# ESP32_USB.net
KiCad netlist of a schematic drawn in Altium Designer
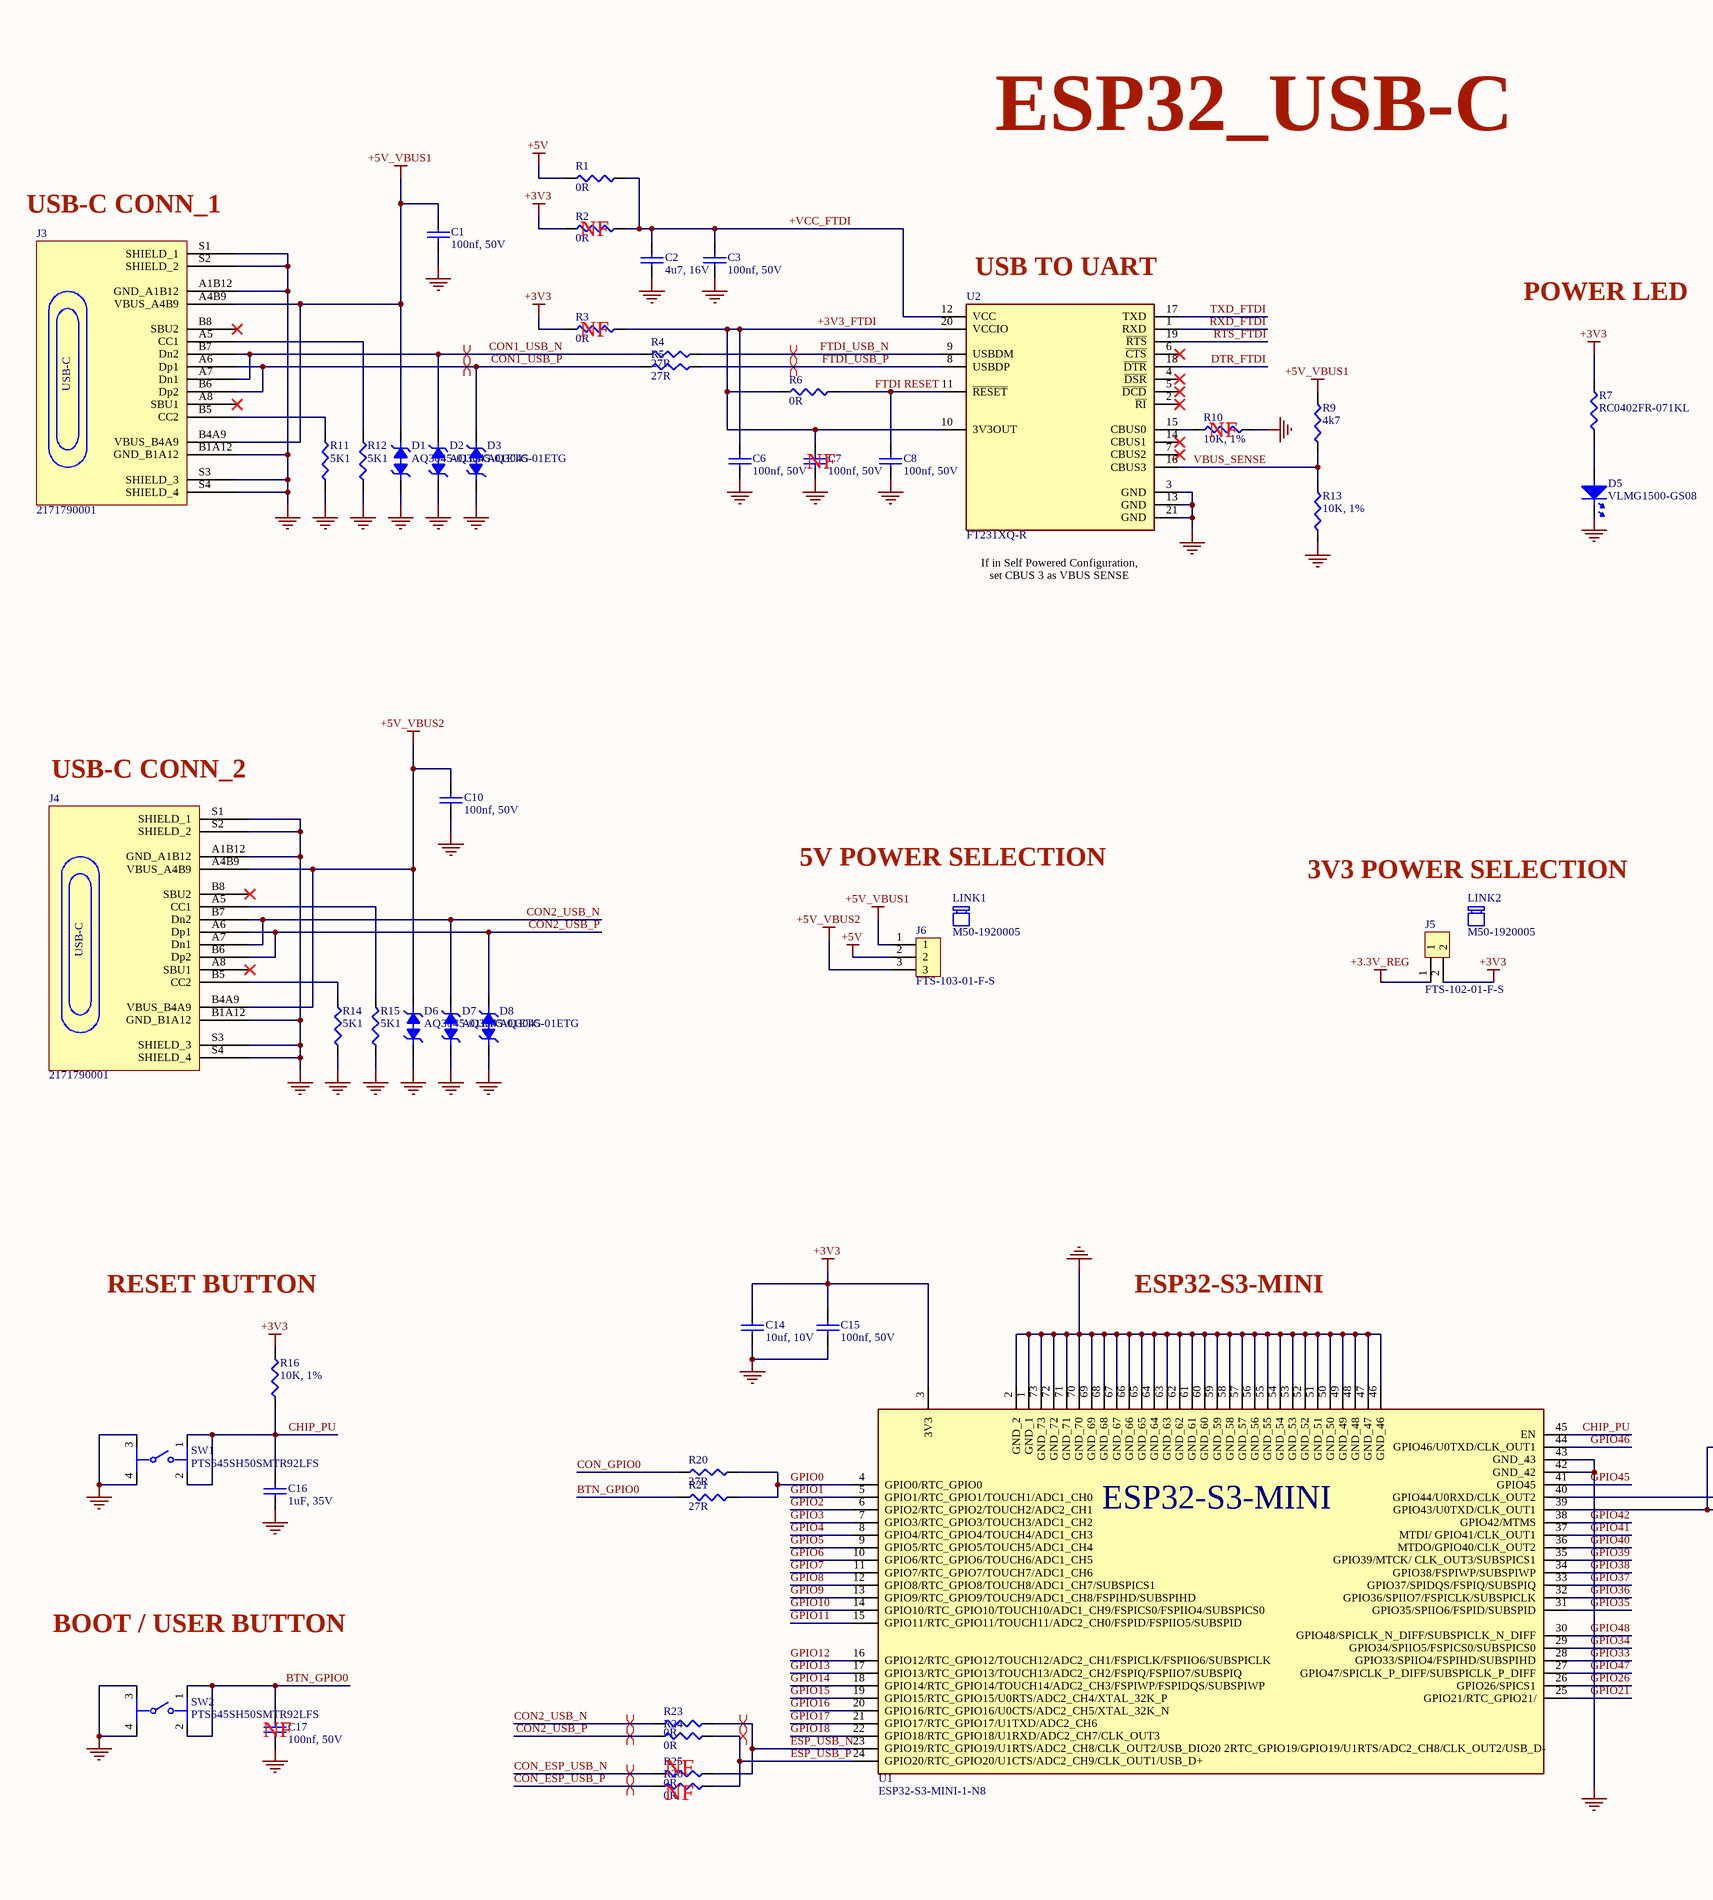
[diagram p0: ESP32_USB.SchDoc, left]
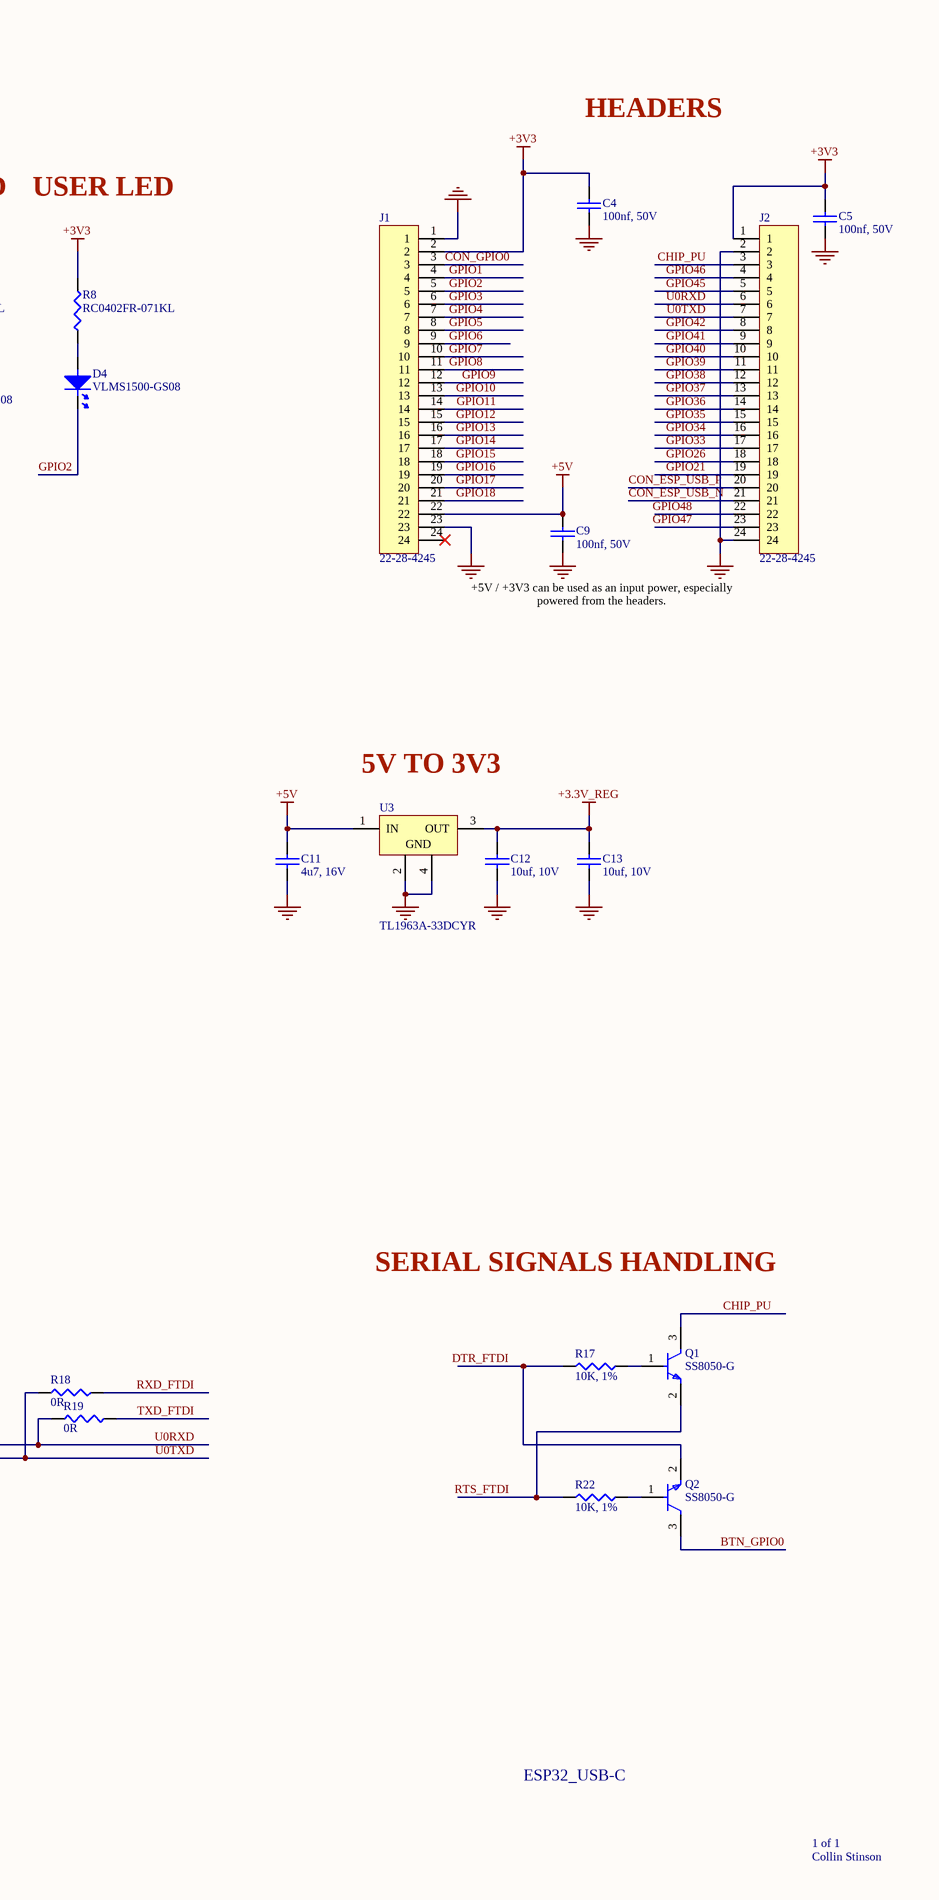
[diagram p1: ESP32_USB.SchDoc, right]

(export (version "E")
  (design (tool "Eeschema 10.0.6"))
  (components
    (comp (ref "C1")
      (value "100nf, 50V")
      (footprint "CAPC1005X65N")
      (fields
        (field (name "MANUFACTURER") "Samsung")
        (field (name "MANUFACTURER PART NUMBER") "CL05B104KB54PNC")
        (field (name "LCSC PART NO") "C307331")
      )
      (libsource (lib "ESP32_USB") (part "CL05B104KB54PNC"))
    )
    (comp (ref "C2")
      (value "4u7, 16V")
      (footprint "CAPC1005X65N")
      (fields
        (field (name "MANUFACTURER") "Samsung")
        (field (name "MANUFACTURER PART NUMBER") "CL05A475MO5NUNC")
        (field (name "LCSC PART NO") "C318563")
      )
      (libsource (lib "ESP32_USB") (part "CL05A475MO5NUNC"))
    )
    (comp (ref "C3")
      (value "100nf, 50V")
      (footprint "CAPC1005X65N")
      (fields
        (field (name "MANUFACTURER") "Samsung")
        (field (name "MANUFACTURER PART NUMBER") "CL05B104KB54PNC")
        (field (name "LCSC PART NO") "C307331")
      )
      (libsource (lib "ESP32_USB") (part "CL05B104KB54PNC"))
    )
    (comp (ref "C4")
      (value "100nf, 50V")
      (footprint "CAPC1005X65N")
      (fields
        (field (name "MANUFACTURER") "Samsung")
        (field (name "MANUFACTURER PART NUMBER") "CL05B104KB54PNC")
        (field (name "LCSC PART NO") "C307331")
      )
      (libsource (lib "ESP32_USB") (part "CL05B104KB54PNC"))
    )
    (comp (ref "C5")
      (value "100nf, 50V")
      (footprint "CAPC1005X65N")
      (fields
        (field (name "MANUFACTURER") "Samsung")
        (field (name "MANUFACTURER PART NUMBER") "CL05B104KB54PNC")
        (field (name "LCSC PART NO") "C307331")
      )
      (libsource (lib "ESP32_USB") (part "CL05B104KB54PNC"))
    )
    (comp (ref "C6")
      (value "100nf, 50V")
      (footprint "CAPC1005X65N")
      (fields
        (field (name "MANUFACTURER") "Samsung")
        (field (name "MANUFACTURER PART NUMBER") "CL05B104KB54PNC")
        (field (name "LCSC PART NO") "C307331")
      )
      (libsource (lib "ESP32_USB") (part "CL05B104KB54PNC"))
    )
    (comp (ref "C7")
      (value "100nf, 50V")
      (footprint "CAPC1005X65N")
      (fields
        (field (name "MANUFACTURER") "Samsung")
        (field (name "MANUFACTURER PART NUMBER") "CL05B104KB54PNC")
        (field (name "LCSC PART NO") "C307331")
      )
      (libsource (lib "ESP32_USB") (part "CL05B104KB54PNC"))
    )
    (comp (ref "C8")
      (value "100nf, 50V")
      (footprint "CAPC1005X65N")
      (fields
        (field (name "MANUFACTURER") "Samsung")
        (field (name "MANUFACTURER PART NUMBER") "CL05B104KB54PNC")
        (field (name "LCSC PART NO") "C307331")
      )
      (libsource (lib "ESP32_USB") (part "CL05B104KB54PNC"))
    )
    (comp (ref "C9")
      (value "100nf, 50V")
      (footprint "CAPC1005X65N")
      (fields
        (field (name "MANUFACTURER") "Samsung")
        (field (name "MANUFACTURER PART NUMBER") "CL05B104KB54PNC")
        (field (name "LCSC PART NO") "C307331")
      )
      (libsource (lib "ESP32_USB") (part "CL05B104KB54PNC"))
    )
    (comp (ref "C10")
      (value "100nf, 50V")
      (footprint "CAPC1005X65N")
      (fields
        (field (name "MANUFACTURER") "Samsung")
        (field (name "MANUFACTURER PART NUMBER") "CL05B104KB54PNC")
        (field (name "LCSC PART NO") "C307331")
      )
      (libsource (lib "ESP32_USB") (part "CL05B104KB54PNC"))
    )
    (comp (ref "C11")
      (value "4u7, 16V")
      (footprint "CAPC1005X65N")
      (fields
        (field (name "MANUFACTURER") "Samsung")
        (field (name "MANUFACTURER PART NUMBER") "CL05A475MO5NUNC")
        (field (name "LCSC PART NO") "C318563")
      )
      (libsource (lib "ESP32_USB") (part "CL05A475MO5NUNC"))
    )
    (comp (ref "C12")
      (value "10uf, 10V")
      (footprint "CAPC1005X65N")
      (fields
        (field (name "MANUFACTURER") "Samsung")
        (field (name "MANUFACTURER PART NUMBER") "CL05A106MP8NUB8")
        (field (name "LCSC PART NO") "C307415")
      )
      (libsource (lib "ESP32_USB") (part "CL05A106MP8NUB8"))
    )
    (comp (ref "C13")
      (value "10uf, 10V")
      (footprint "CAPC1005X65N")
      (fields
        (field (name "MANUFACTURER") "Samsung")
        (field (name "MANUFACTURER PART NUMBER") "CL05A106MP8NUB8")
        (field (name "LCSC PART NO") "C307415")
      )
      (libsource (lib "ESP32_USB") (part "CL05A106MP8NUB8"))
    )
    (comp (ref "C14")
      (value "10uf, 10V")
      (footprint "CAPC1005X65N")
      (fields
        (field (name "MANUFACTURER") "Samsung")
        (field (name "MANUFACTURER PART NUMBER") "CL05A106MP8NUB8")
        (field (name "LCSC PART NO") "C307415")
      )
      (libsource (lib "ESP32_USB") (part "CL05A106MP8NUB8"))
    )
    (comp (ref "C15")
      (value "100nf, 50V")
      (footprint "CAPC1005X65N")
      (fields
        (field (name "MANUFACTURER") "Samsung")
        (field (name "MANUFACTURER PART NUMBER") "CL05B104KB54PNC")
        (field (name "LCSC PART NO") "C307331")
      )
      (libsource (lib "ESP32_USB") (part "CL05B104KB54PNC"))
    )
    (comp (ref "C16")
      (value "1uF, 35V")
      (footprint "CAPC1005X65N")
      (fields
        (field (name "MANUFACTURER") "Samsung")
        (field (name "MANUFACTURER PART NUMBER") "CL05A105KL5NRNC")
        (field (name "LCSC PART NO") "C307413")
      )
      (libsource (lib "ESP32_USB") (part "CL05A105KL5NRNC"))
    )
    (comp (ref "C17")
      (value "100nf, 50V")
      (footprint "CAPC1005X65N")
      (fields
        (field (name "MANUFACTURER") "Samsung")
        (field (name "MANUFACTURER PART NUMBER") "CL05B104KB54PNC")
        (field (name "LCSC PART NO") "C307331")
      )
      (libsource (lib "ESP32_USB") (part "CL05B104KB54PNC"))
    )
    (comp (ref "D1")
      (value "AQ3045-01ETG")
      (footprint "SOD882")
      (description "Trans Voltage Suppressor Diode, 40W, 5.3V V(RWM), Bidirectional, 1 Element, Silicon, MO-236")
      (fields (field (name "MANUFACTURER") "Littelfuse") (field (name "LCSC PART NO") "C3710326"))
      (libsource (lib "ESP32_USB") (part "AQ3045-01ETG"))
    )
    (comp (ref "D2")
      (value "AQ3045-01ETG")
      (footprint "SOD882")
      (description "Trans Voltage Suppressor Diode, 40W, 5.3V V(RWM), Bidirectional, 1 Element, Silicon, MO-236")
      (fields (field (name "MANUFACTURER") "Littelfuse") (field (name "LCSC PART NO") "C3710326"))
      (libsource (lib "ESP32_USB") (part "AQ3045-01ETG"))
    )
    (comp (ref "D3")
      (value "AQ3045-01ETG")
      (footprint "SOD882")
      (description "Trans Voltage Suppressor Diode, 40W, 5.3V V(RWM), Bidirectional, 1 Element, Silicon, MO-236")
      (fields (field (name "MANUFACTURER") "Littelfuse") (field (name "LCSC PART NO") "C3710326"))
      (libsource (lib "ESP32_USB") (part "AQ3045-01ETG"))
    )
    (comp (ref "D4")
      (value "VLMS1500-GS08")
      (footprint "LEDC1005X35N")
      (description "Single Color LED, Super Red, 0.5mm")
      (fields (field (name "MANUFACTURER") "Vishay") (field (name "LCSC PART NO") "C511370"))
      (libsource (lib "ESP32_USB") (part "VLMS1500-GS08"))
    )
    (comp (ref "D5")
      (value "VLMG1500-GS08")
      (footprint "LEDC1005X35N")
      (description "Single Color LED, Yellow Green, 0.5mm")
      (fields (field (name "MANUFACTURER") "Vishay") (field (name "LCSC PART NO") "C511404"))
      (libsource (lib "ESP32_USB") (part "VLMG1500-GS08"))
    )
    (comp (ref "D6")
      (value "AQ3045-01ETG")
      (footprint "SOD882")
      (description "Trans Voltage Suppressor Diode, 40W, 5.3V V(RWM), Bidirectional, 1 Element, Silicon, MO-236")
      (fields (field (name "MANUFACTURER") "Littelfuse") (field (name "LCSC PART NO") "C3710326"))
      (libsource (lib "ESP32_USB") (part "AQ3045-01ETG"))
    )
    (comp (ref "D7")
      (value "AQ3045-01ETG")
      (footprint "SOD882")
      (description "Trans Voltage Suppressor Diode, 40W, 5.3V V(RWM), Bidirectional, 1 Element, Silicon, MO-236")
      (fields (field (name "MANUFACTURER") "Littelfuse") (field (name "LCSC PART NO") "C3710326"))
      (libsource (lib "ESP32_USB") (part "AQ3045-01ETG"))
    )
    (comp (ref "D8")
      (value "AQ3045-01ETG")
      (footprint "SOD882")
      (description "Trans Voltage Suppressor Diode, 40W, 5.3V V(RWM), Bidirectional, 1 Element, Silicon, MO-236")
      (fields (field (name "MANUFACTURER") "Littelfuse") (field (name "LCSC PART NO") "C3710326"))
      (libsource (lib "ESP32_USB") (part "AQ3045-01ETG"))
    )
    (comp (ref "J1")
      (value "22-28-4245")
      (footprint "HDR_1X24_2.54MM")
      (description "Conn Unshrouded Header HDR 24 POS 2.54mm Solder ST Thru-Hole KK® Bag")
      (fields (field (name "MANUFACTURER") "Molex") (field (name "LCSC PART NO") "C7145888"))
      (libsource (lib "ESP32_USB") (part "22-28-4245"))
    )
    (comp (ref "J2")
      (value "22-28-4245")
      (footprint "HDR_1X24_2.54MM")
      (description "Conn Unshrouded Header HDR 24 POS 2.54mm Solder ST Thru-Hole KK® Bag")
      (fields (field (name "MANUFACTURER") "Molex") (field (name "LCSC PART NO") "C7145888"))
      (libsource (lib "") (part "22-28-4245_1"))
    )
    (comp (ref "J3")
      (value "2171790001")
      (footprint "FP-2171790001-MFG")
      (description "USB Connector, 16 Contact(s), Female, Right Angle, Surface Mount Terminal, Locking, Receptacle")
      (fields (field (name "MANUFACTURER") "Molex") (field (name "MANUFACTURER PART NUMBER") "217179-0001"))
      (libsource (lib "ESP32_USB") (part "217179-0001"))
    )
    (comp (ref "J4")
      (value "2171790001")
      (footprint "FP-2171790001-MFG")
      (description "USB Connector, 16 Contact(s), Female, Right Angle, Surface Mount Terminal, Locking, Receptacle")
      (fields (field (name "MANUFACTURER") "Molex") (field (name "MANUFACTURER PART NUMBER") "217179-0001"))
      (libsource (lib "ESP32_USB") (part "217179-0001"))
    )
    (comp (ref "J5")
      (value "FTS-102-01-F-S")
      (footprint "HDR_1X2_1.27MM")
      (description "Board Connector, 2 Contact(s), 1 Row(s), Male, Straight, Solder Terminal")
      (fields (field (name "MANUFACTURER") "Samtec") (field (name "LCSC PART NO") "C6045317"))
      (libsource (lib "ESP32_USB") (part "FTS-102-01-F-S"))
    )
    (comp (ref "J6")
      (value "FTS-103-01-F-S")
      (footprint "HDR_1X3_1.27MM")
      (description "Board Connector, 3 Contact(s), 1 Row(s), Male, Straight, Solder Terminal")
      (fields (field (name "MANUFACTURER") "Samtec") (field (name "LCSC PART NO") "C3333578"))
      (libsource (lib "ESP32_USB") (part "FTS-103-01-F-S"))
    )
    (comp (ref "LINK1")
      (value "M50-1920005")
      (description "Interconnection Device")
      (fields (field (name "MANUFACTURER") "Harwin") (field (name "LCSC PART NO") "C6985646"))
      (libsource (lib "ESP32_USB") (part "M50-1920005"))
    )
    (comp (ref "LINK2")
      (value "M50-1920005")
      (description "Interconnection Device")
      (fields (field (name "MANUFACTURER") "Harwin") (field (name "LCSC PART NO") "C6985646"))
      (libsource (lib "ESP32_USB") (part "M50-1920005"))
    )
    (comp (ref "Q1")
      (value "SS8050-G")
      (footprint "FP-SS8050-G-IPC_B")
      (description "Small Signal Bipolar Transistor, 1.5A I(C), 25V V(BR)CEO, 1-Element, NPN, Silicon")
      (fields (field (name "MANUFACTURER") "Comchip") (field (name "LCSC PART NO") "C164886"))
      (libsource (lib "ESP32_USB") (part "SS8050-G"))
    )
    (comp (ref "Q2")
      (value "SS8050-G")
      (footprint "FP-SS8050-G-IPC_B")
      (description "Small Signal Bipolar Transistor, 1.5A I(C), 25V V(BR)CEO, 1-Element, NPN, Silicon")
      (fields (field (name "MANUFACTURER") "Comchip") (field (name "LCSC PART NO") "C164886"))
      (libsource (lib "ESP32_USB") (part "SS8050-G"))
    )
    (comp (ref "R1")
      (value "0R")
      (footprint "RESC1005X37N")
      (description "Metal Glaze/thick Film, 0.0625W, 0ohm, Surface Mount, 0402")
      (fields
        (field (name "MANUFACTURER") "Yageo")
        (field (name "MANUFACTURER PART NUMBER") "RC0402JR-070RL")
      )
      (libsource (lib "ESP32_USB") (part "RC0402JR-070RL"))
    )
    (comp (ref "R2")
      (value "0R")
      (footprint "RESC1005X37N")
      (description "Metal Glaze/thick Film, 0.0625W, 0ohm, Surface Mount, 0402")
      (fields
        (field (name "MANUFACTURER") "Yageo")
        (field (name "MANUFACTURER PART NUMBER") "RC0402JR-070RL")
      )
      (libsource (lib "ESP32_USB") (part "RC0402JR-070RL"))
    )
    (comp (ref "R3")
      (value "0R")
      (footprint "RESC1005X37N")
      (description "Metal Glaze/thick Film, 0.0625W, 0ohm, Surface Mount, 0402")
      (fields
        (field (name "MANUFACTURER") "Yageo")
        (field (name "MANUFACTURER PART NUMBER") "RC0402JR-070RL")
      )
      (libsource (lib "ESP32_USB") (part "RC0402JR-070RL"))
    )
    (comp (ref "R4")
      (value "27R")
      (footprint "RESC1005X37N")
      (fields
        (field (name "MANUFACTURER") "Yageo")
        (field (name "MANUFACTURER PART NUMBER") "RC0402FR-0727RL")
        (field (name "TOLERANCE") "1%")
      )
      (libsource (lib "ESP32_USB") (part "RC0402FR-0727RL"))
    )
    (comp (ref "R5")
      (value "27R")
      (footprint "RESC1005X37N")
      (fields
        (field (name "MANUFACTURER") "Yageo")
        (field (name "MANUFACTURER PART NUMBER") "RC0402FR-0727RL")
        (field (name "TOLERANCE") "1%")
      )
      (libsource (lib "ESP32_USB") (part "RC0402FR-0727RL"))
    )
    (comp (ref "R6")
      (value "0R")
      (footprint "RESC1005X37N")
      (description "Metal Glaze/thick Film, 0.0625W, 0ohm, Surface Mount, 0402")
      (fields
        (field (name "MANUFACTURER") "Yageo")
        (field (name "MANUFACTURER PART NUMBER") "RC0402JR-070RL")
      )
      (libsource (lib "ESP32_USB") (part "RC0402JR-070RL"))
    )
    (comp (ref "R7")
      (value "RC0402FR-071KL")
      (footprint "RESC1005X37N")
      (fields
        (field (name "MANUFACTURER") "Yageo")
        (field (name "TOLERANCE") "1%")
        (field (name "POWER") "62.5mW")
      )
      (libsource (lib "ESP32_USB") (part "RC0402FR-071KL"))
    )
    (comp (ref "R8")
      (value "RC0402FR-071KL")
      (footprint "RESC1005X37N")
      (fields
        (field (name "MANUFACTURER") "Yageo")
        (field (name "TOLERANCE") "1%")
        (field (name "POWER") "62.5mW")
      )
      (libsource (lib "ESP32_USB") (part "RC0402FR-071KL"))
    )
    (comp (ref "R9")
      (value "4k7")
      (footprint "RESC1005X37N")
      (fields
        (field (name "MANUFACTURER") "Yageo")
        (field (name "MANUFACTURER PART NUMBER") "RC0402FR-074K7L")
        (field (name "TOLERANCE") "1%")
      )
      (libsource (lib "ESP32_USB") (part "RC0402FR-074K7L"))
    )
    (comp (ref "R10")
      (value "10K, 1%")
      (footprint "RESC1005X37N")
      (fields
        (field (name "MANUFACTURER") "Yageo")
        (field (name "MANUFACTURER PART NUMBER") "AC0402FR-0710KL")
        (field (name "TOLERANCE") "1%")
      )
      (libsource (lib "ESP32_USB") (part "AC0402FR-0710KL"))
    )
    (comp (ref "R11")
      (value "5K1")
      (footprint "RESC1005X37N")
      (fields
        (field (name "MANUFACTURER") "Yageo")
        (field (name "MANUFACTURER PART NUMBER") "AC0402FR-075K1L")
        (field (name "TOLERANCE") "1%")
      )
      (libsource (lib "ESP32_USB") (part "AC0402FR-075K1L"))
    )
    (comp (ref "R12")
      (value "5K1")
      (footprint "RESC1005X37N")
      (fields
        (field (name "MANUFACTURER") "Yageo")
        (field (name "MANUFACTURER PART NUMBER") "AC0402FR-075K1L")
        (field (name "TOLERANCE") "1%")
      )
      (libsource (lib "ESP32_USB") (part "AC0402FR-075K1L"))
    )
    (comp (ref "R13")
      (value "10K, 1%")
      (footprint "RESC1005X37N")
      (fields
        (field (name "MANUFACTURER") "Yageo")
        (field (name "MANUFACTURER PART NUMBER") "AC0402FR-0710KL")
        (field (name "TOLERANCE") "1%")
      )
      (libsource (lib "ESP32_USB") (part "AC0402FR-0710KL"))
    )
    (comp (ref "R14")
      (value "5K1")
      (footprint "RESC1005X37N")
      (fields
        (field (name "MANUFACTURER") "Yageo")
        (field (name "MANUFACTURER PART NUMBER") "AC0402FR-075K1L")
        (field (name "TOLERANCE") "1%")
      )
      (libsource (lib "ESP32_USB") (part "AC0402FR-075K1L"))
    )
    (comp (ref "R15")
      (value "5K1")
      (footprint "RESC1005X37N")
      (fields
        (field (name "MANUFACTURER") "Yageo")
        (field (name "MANUFACTURER PART NUMBER") "AC0402FR-075K1L")
        (field (name "TOLERANCE") "1%")
      )
      (libsource (lib "ESP32_USB") (part "AC0402FR-075K1L"))
    )
    (comp (ref "R16")
      (value "10K, 1%")
      (footprint "RESC1005X37N")
      (fields
        (field (name "MANUFACTURER") "Yageo")
        (field (name "MANUFACTURER PART NUMBER") "AC0402FR-0710KL")
        (field (name "TOLERANCE") "1%")
      )
      (libsource (lib "ESP32_USB") (part "AC0402FR-0710KL"))
    )
    (comp (ref "R17")
      (value "10K, 1%")
      (footprint "RESC1005X37N")
      (fields
        (field (name "MANUFACTURER") "Yageo")
        (field (name "MANUFACTURER PART NUMBER") "AC0402FR-0710KL")
        (field (name "TOLERANCE") "1%")
      )
      (libsource (lib "ESP32_USB") (part "AC0402FR-0710KL"))
    )
    (comp (ref "R18")
      (value "0R")
      (footprint "RESC1005X37N")
      (description "Metal Glaze/thick Film, 0.0625W, 0ohm, Surface Mount, 0402")
      (fields
        (field (name "MANUFACTURER") "Yageo")
        (field (name "MANUFACTURER PART NUMBER") "RC0402JR-070RL")
      )
      (libsource (lib "ESP32_USB") (part "RC0402JR-070RL"))
    )
    (comp (ref "R19")
      (value "0R")
      (footprint "RESC1005X37N")
      (description "Metal Glaze/thick Film, 0.0625W, 0ohm, Surface Mount, 0402")
      (fields
        (field (name "MANUFACTURER") "Yageo")
        (field (name "MANUFACTURER PART NUMBER") "RC0402JR-070RL")
      )
      (libsource (lib "ESP32_USB") (part "RC0402JR-070RL"))
    )
    (comp (ref "R20")
      (value "27R")
      (footprint "RESC1005X37N")
      (fields
        (field (name "MANUFACTURER") "Yageo")
        (field (name "MANUFACTURER PART NUMBER") "RC0402FR-0727RL")
        (field (name "TOLERANCE") "1%")
      )
      (libsource (lib "ESP32_USB") (part "RC0402FR-0727RL"))
    )
    (comp (ref "R21")
      (value "27R")
      (footprint "RESC1005X37N")
      (fields
        (field (name "MANUFACTURER") "Yageo")
        (field (name "MANUFACTURER PART NUMBER") "RC0402FR-0727RL")
        (field (name "TOLERANCE") "1%")
      )
      (libsource (lib "ESP32_USB") (part "RC0402FR-0727RL"))
    )
    (comp (ref "R22")
      (value "10K, 1%")
      (footprint "RESC1005X37N")
      (fields
        (field (name "MANUFACTURER") "Yageo")
        (field (name "MANUFACTURER PART NUMBER") "AC0402FR-0710KL")
        (field (name "TOLERANCE") "1%")
      )
      (libsource (lib "ESP32_USB") (part "AC0402FR-0710KL"))
    )
    (comp (ref "R23")
      (value "0R")
      (footprint "RESC1005X37N")
      (description "Metal Glaze/thick Film, 0.0625W, 0ohm, Surface Mount, 0402")
      (fields
        (field (name "MANUFACTURER") "Yageo")
        (field (name "MANUFACTURER PART NUMBER") "RC0402JR-070RL")
      )
      (libsource (lib "ESP32_USB") (part "RC0402JR-070RL"))
    )
    (comp (ref "R24")
      (value "0R")
      (footprint "RESC1005X37N")
      (description "Metal Glaze/thick Film, 0.0625W, 0ohm, Surface Mount, 0402")
      (fields
        (field (name "MANUFACTURER") "Yageo")
        (field (name "MANUFACTURER PART NUMBER") "RC0402JR-070RL")
      )
      (libsource (lib "ESP32_USB") (part "RC0402JR-070RL"))
    )
    (comp (ref "R25")
      (value "0R")
      (footprint "RESC1005X37N")
      (description "Metal Glaze/thick Film, 0.0625W, 0ohm, Surface Mount, 0402")
      (fields
        (field (name "MANUFACTURER") "Yageo")
        (field (name "MANUFACTURER PART NUMBER") "RC0402JR-070RL")
      )
      (libsource (lib "ESP32_USB") (part "RC0402JR-070RL"))
    )
    (comp (ref "R26")
      (value "0R")
      (footprint "RESC1005X37N")
      (description "Metal Glaze/thick Film, 0.0625W, 0ohm, Surface Mount, 0402")
      (fields
        (field (name "MANUFACTURER") "Yageo")
        (field (name "MANUFACTURER PART NUMBER") "RC0402JR-070RL")
      )
      (libsource (lib "ESP32_USB") (part "RC0402JR-070RL"))
    )
    (comp (ref "SW1")
      (value "PTS645SH50SMTR92LFS")
      (footprint "FP-PTS645SH50SMTR92LFS-MFG")
      (fields (field (name "MANUFACTURER") "ITT C&K") (field (name "LCSC PART NO") "C221869"))
      (libsource (lib "ESP32_USB") (part "PTS645SH50SMTR92LFS"))
    )
    (comp (ref "SW2")
      (value "PTS645SH50SMTR92LFS")
      (footprint "FP-PTS645SH50SMTR92LFS-MFG")
      (fields (field (name "MANUFACTURER") "ITT C&K") (field (name "LCSC PART NO") "C221869"))
      (libsource (lib "ESP32_USB") (part "PTS645SH50SMTR92LFS"))
    )
    (comp (ref "U1")
      (value "ESP32-S3-MINI-1-N8")
      (footprint "XCVR_ESP32-S3-MINI-1-N8")
      (description "SMD module, ESP32-S3FN8, 8 MB SPI flash, PCB antenna")
      (fields (field (name "MANUFACTURER") "Espressif Systems") (field (name "LCSC PART NO") "C2913206"))
      (libsource (lib "ESP32_USB") (part "ESP32-S3-MINI-1-N8"))
    )
    (comp (ref "U2")
      (value "FT231XQ-R")
      (footprint "FP-QFN-20-IPC_B")
      (description "Microprocessor Circuit, CMOS")
      (fields (field (name "MANUFACTURER") "FTDI") (field (name "LCSC PART NO") "C132159"))
      (libsource (lib "ESP32_USB") (part "FT231XQ-R"))
    )
    (comp (ref "U3")
      (value "TL1963A-33DCYR")
      (footprint "DCY0004A_N")
      (description "Fixed Positive LDO Regulator, 3.3V, 0.55V Dropout, BIPolar, PDSO4")
      (fields (field (name "MANUFACTURER") "Texas Instruments") (field (name "LCSC PART NO") "C181262"))
      (libsource (lib "ESP32_USB") (part "TL1963A-33DCYR"))
    )
  )
  (nets
    (net (code "1") (name "+3.3V_REG") (class "Default")
      (node (ref "C12") (pin "2") (pinfunction "2_2") (pintype "passive"))
      (node (ref "C13") (pin "2") (pinfunction "2_2") (pintype "passive"))
      (node (ref "J5") (pin "1") (pinfunction "1_1") (pintype "passive"))
      (node (ref "U3") (pin "3") (pinfunction "OUT_3") (pintype "power_in"))
    )
    (net (code "2") (name "+3V3") (class "Default")
      (node (ref "C14") (pin "2") (pinfunction "2_2") (pintype "passive"))
      (node (ref "C15") (pin "2") (pinfunction "2_2") (pintype "passive"))
      (node (ref "C4") (pin "2") (pinfunction "2_2") (pintype "passive"))
      (node (ref "C5") (pin "2") (pinfunction "2_2") (pintype "passive"))
      (node (ref "J1") (pin "2") (pinfunction "2_2") (pintype "passive"))
      (node (ref "J2") (pin "1") (pinfunction "1_1") (pintype "passive"))
      (node (ref "J5") (pin "2") (pinfunction "2_2") (pintype "passive"))
      (node (ref "R16") (pin "1") (pinfunction "1_1") (pintype "passive"))
      (node (ref "R2") (pin "1") (pinfunction "1_1") (pintype "passive"))
      (node (ref "R3") (pin "1") (pinfunction "1_1") (pintype "passive"))
      (node (ref "R7") (pin "2") (pinfunction "2_2") (pintype "passive"))
      (node (ref "R8") (pin "2") (pinfunction "2_2") (pintype "passive"))
      (node (ref "U1") (pin "3") (pinfunction "3V3_3") (pintype "passive"))
    )
    (net (code "3") (name "+5V") (class "Default")
      (node (ref "C11") (pin "1") (pinfunction "1_1") (pintype "passive"))
      (node (ref "C9") (pin "2") (pinfunction "2_2") (pintype "passive"))
      (node (ref "J1") (pin "22") (pinfunction "22_22") (pintype "passive"))
      (node (ref "J6") (pin "2") (pinfunction "2_2") (pintype "passive"))
      (node (ref "R1") (pin "1") (pinfunction "1_1") (pintype "passive"))
      (node (ref "U3") (pin "1") (pinfunction "IN_1") (pintype "power_in"))
    )
    (net (code "4") (name "+5V_VBUS1") (class "Default")
      (node (ref "C1") (pin "2") (pinfunction "2_2") (pintype "passive"))
      (node (ref "D1") (pin "2") (pinfunction "2_2") (pintype "passive"))
      (node (ref "J3") (pin "A4B9") (pinfunction "VBUS_A4B9_A4B9") (pintype "passive"))
      (node (ref "J3") (pin "B4A9") (pinfunction "VBUS_B4A9_B4A9") (pintype "passive"))
      (node (ref "J6") (pin "1") (pinfunction "1_1") (pintype "passive"))
      (node (ref "R9") (pin "2") (pinfunction "2_2") (pintype "passive"))
    )
    (net (code "5") (name "+5V_VBUS2") (class "Default")
      (node (ref "C10") (pin "2") (pinfunction "2_2") (pintype "passive"))
      (node (ref "D6") (pin "2") (pinfunction "2_2") (pintype "passive"))
      (node (ref "J4") (pin "A4B9") (pinfunction "VBUS_A4B9_A4B9") (pintype "passive"))
      (node (ref "J4") (pin "B4A9") (pinfunction "VBUS_B4A9_B4A9") (pintype "passive"))
      (node (ref "J6") (pin "3") (pinfunction "3_3") (pintype "passive"))
    )
    (net (code "6") (name "/+3V3_FTDI") (class "Default")
      (node (ref "C6") (pin "2") (pinfunction "2_2") (pintype "passive"))
      (node (ref "C7") (pin "2") (pinfunction "2_2") (pintype "passive"))
      (node (ref "R3") (pin "2") (pinfunction "2_2") (pintype "passive"))
      (node (ref "R6") (pin "1") (pinfunction "1_1") (pintype "passive"))
      (node (ref "U2") (pin "10") (pinfunction "3V3OUT_10") (pintype "passive"))
      (node (ref "U2") (pin "20") (pinfunction "VCCIO_20") (pintype "passive"))
    )
    (net (code "7") (name "/+VCC_FTDI") (class "Default")
      (node (ref "C2") (pin "2") (pinfunction "2_2") (pintype "passive"))
      (node (ref "C3") (pin "2") (pinfunction "2_2") (pintype "passive"))
      (node (ref "R1") (pin "2") (pinfunction "2_2") (pintype "passive"))
      (node (ref "R2") (pin "2") (pinfunction "2_2") (pintype "passive"))
      (node (ref "U2") (pin "12") (pinfunction "VCC_12") (pintype "passive"))
    )
    (net (code "8") (name "/BTN_GPIO0") (class "Default")
      (node (ref "C17") (pin "2") (pinfunction "2_2") (pintype "passive"))
      (node (ref "Q2") (pin "3") (pinfunction "C_3") (pintype "passive"))
      (node (ref "R21") (pin "1") (pinfunction "1_1") (pintype "passive"))
      (node (ref "SW2") (pin "1") (pinfunction "1_1") (pintype "passive"))
      (node (ref "SW2") (pin "2") (pinfunction "2_2") (pintype "passive"))
    )
    (net (code "9") (name "/CHIP_PU") (class "Default")
      (node (ref "C16") (pin "2") (pinfunction "2_2") (pintype "passive"))
      (node (ref "J2") (pin "3") (pinfunction "3_3") (pintype "passive"))
      (node (ref "Q1") (pin "3") (pinfunction "C_3") (pintype "passive"))
      (node (ref "R16") (pin "2") (pinfunction "2_2") (pintype "passive"))
      (node (ref "SW1") (pin "1") (pinfunction "1_1") (pintype "passive"))
      (node (ref "SW1") (pin "2") (pinfunction "2_2") (pintype "passive"))
      (node (ref "U1") (pin "45") (pinfunction "EN_45") (pintype "passive"))
    )
    (net (code "10") (name "/CON1_USB_N") (class "Default")
      (node (ref "D2") (pin "2") (pinfunction "2_2") (pintype "passive"))
      (node (ref "J3") (pin "A7") (pinfunction "Dn1_A7") (pintype "passive"))
      (node (ref "J3") (pin "B7") (pinfunction "Dn2_B7") (pintype "passive"))
      (node (ref "R4") (pin "1") (pinfunction "1_1") (pintype "passive"))
    )
    (net (code "11") (name "/CON1_USB_P") (class "Default")
      (node (ref "D3") (pin "2") (pinfunction "2_2") (pintype "passive"))
      (node (ref "J3") (pin "A6") (pinfunction "Dp1_A6") (pintype "passive"))
      (node (ref "J3") (pin "B6") (pinfunction "Dp2_B6") (pintype "passive"))
      (node (ref "R5") (pin "1") (pinfunction "1_1") (pintype "passive"))
    )
    (net (code "12") (name "/CON2_USB_N") (class "Default")
      (node (ref "D7") (pin "2") (pinfunction "2_2") (pintype "passive"))
      (node (ref "J4") (pin "A7") (pinfunction "Dn1_A7") (pintype "passive"))
      (node (ref "J4") (pin "B7") (pinfunction "Dn2_B7") (pintype "passive"))
      (node (ref "R23") (pin "1") (pinfunction "1_1") (pintype "passive"))
    )
    (net (code "13") (name "/CON2_USB_P") (class "Default")
      (node (ref "D8") (pin "2") (pinfunction "2_2") (pintype "passive"))
      (node (ref "J4") (pin "A6") (pinfunction "Dp1_A6") (pintype "passive"))
      (node (ref "J4") (pin "B6") (pinfunction "Dp2_B6") (pintype "passive"))
      (node (ref "R24") (pin "1") (pinfunction "1_1") (pintype "passive"))
    )
    (net (code "14") (name "/CON_ESP_USB_N") (class "Default")
      (node (ref "J2") (pin "21") (pinfunction "21_21") (pintype "passive"))
      (node (ref "R25") (pin "1") (pinfunction "1_1") (pintype "passive"))
    )
    (net (code "15") (name "/CON_ESP_USB_P") (class "Default")
      (node (ref "J2") (pin "20") (pinfunction "20_20") (pintype "passive"))
      (node (ref "R26") (pin "1") (pinfunction "1_1") (pintype "passive"))
    )
    (net (code "16") (name "/CON_GPIO0") (class "Default")
      (node (ref "J1") (pin "3") (pinfunction "3_3") (pintype "passive"))
      (node (ref "R20") (pin "1") (pinfunction "1_1") (pintype "passive"))
    )
    (net (code "17") (name "/DTR_FTDI") (class "Default")
      (node (ref "Q2") (pin "2") (pinfunction "E_2") (pintype "passive"))
      (node (ref "R17") (pin "1") (pinfunction "1_1") (pintype "passive"))
      (node (ref "U2") (pin "18") (pinfunction "~{DTR}_18") (pintype "passive"))
    )
    (net (code "18") (name "/ESP_USB_N") (class "Default")
      (node (ref "R23") (pin "2") (pinfunction "2_2") (pintype "passive"))
      (node (ref "R25") (pin "2") (pinfunction "2_2") (pintype "passive"))
      (node (ref "U1") (pin "23") (pinfunction "GPIO19/RTC_GPIO19/U1RTS/ADC2_CH8/CLK_OUT2/USB_DIO20_2RTC_GPIO19/GPIO19/U1RTS/ADC2_CH8/CLK_OUT2/USB_D-_23") (pintype "passive"))
    )
    (net (code "19") (name "/ESP_USB_P") (class "Default")
      (node (ref "R24") (pin "2") (pinfunction "2_2") (pintype "passive"))
      (node (ref "R26") (pin "2") (pinfunction "2_2") (pintype "passive"))
      (node (ref "U1") (pin "24") (pinfunction "GPIO20/RTC_GPIO20/U1CTS/ADC2_CH9/CLK_OUT1/USB_D+_24") (pintype "passive"))
    )
    (net (code "20") (name "/FTDI RESET") (class "Default")
      (node (ref "C8") (pin "2") (pinfunction "2_2") (pintype "passive"))
      (node (ref "R6") (pin "2") (pinfunction "2_2") (pintype "passive"))
      (node (ref "U2") (pin "11") (pinfunction "~{RESET}_11") (pintype "passive"))
    )
    (net (code "21") (name "/FTDI_USB_N") (class "Default")
      (node (ref "R4") (pin "2") (pinfunction "2_2") (pintype "passive"))
      (node (ref "U2") (pin "9") (pinfunction "USBDM_9") (pintype "passive"))
    )
    (net (code "22") (name "/FTDI_USB_P") (class "Default")
      (node (ref "R5") (pin "2") (pinfunction "2_2") (pintype "passive"))
      (node (ref "U2") (pin "8") (pinfunction "USBDP_8") (pintype "passive"))
    )
    (net (code "23") (name "/GPIO0") (class "Default")
      (node (ref "R20") (pin "2") (pinfunction "2_2") (pintype "passive"))
      (node (ref "R21") (pin "2") (pinfunction "2_2") (pintype "passive"))
      (node (ref "U1") (pin "4") (pinfunction "GPIO0/RTC_GPIO0_4") (pintype "passive"))
    )
    (net (code "24") (name "/GPIO1") (class "Default")
      (node (ref "J1") (pin "4") (pinfunction "4_4") (pintype "passive"))
      (node (ref "U1") (pin "5") (pinfunction "GPIO1/RTC_GPIO1/TOUCH1/ADC1_CH0_5") (pintype "passive"))
    )
    (net (code "25") (name "/GPIO2") (class "Default")
      (node (ref "D4") (pin "2") (pinfunction "2_2") (pintype "passive"))
      (node (ref "J1") (pin "5") (pinfunction "5_5") (pintype "passive"))
      (node (ref "U1") (pin "6") (pinfunction "GPIO2/RTC_GPIO2/TOUCH2/ADC2_CH1_6") (pintype "passive"))
    )
    (net (code "26") (name "/GPIO3") (class "Default")
      (node (ref "J1") (pin "6") (pinfunction "6_6") (pintype "passive"))
      (node (ref "U1") (pin "7") (pinfunction "GPIO3/RTC_GPIO3/TOUCH3/ADC1_CH2_7") (pintype "passive"))
    )
    (net (code "27") (name "/GPIO4") (class "Default")
      (node (ref "J1") (pin "7") (pinfunction "7_7") (pintype "passive"))
      (node (ref "U1") (pin "8") (pinfunction "GPIO4/RTC_GPIO4/TOUCH4/ADC1_CH3_8") (pintype "passive"))
    )
    (net (code "28") (name "/GPIO5") (class "Default")
      (node (ref "J1") (pin "8") (pinfunction "8_8") (pintype "passive"))
      (node (ref "U1") (pin "9") (pinfunction "GPIO5/RTC_GPIO5/TOUCH5/ADC1_CH4_9") (pintype "passive"))
    )
    (net (code "29") (name "/GPIO6") (class "Default")
      (node (ref "J1") (pin "9") (pinfunction "9_9") (pintype "passive"))
      (node (ref "U1") (pin "10") (pinfunction "GPIO6/RTC_GPIO6/TOUCH6/ADC1_CH5_10") (pintype "passive"))
    )
    (net (code "30") (name "/GPIO7") (class "Default")
      (node (ref "J1") (pin "10") (pinfunction "10_10") (pintype "passive"))
      (node (ref "U1") (pin "11") (pinfunction "GPIO7/RTC_GPIO7/TOUCH7/ADC1_CH6_11") (pintype "passive"))
    )
    (net (code "31") (name "/GPIO8") (class "Default")
      (node (ref "J1") (pin "11") (pinfunction "11_11") (pintype "passive"))
      (node (ref "U1") (pin "12") (pinfunction "GPIO8/RTC_GPIO8/TOUCH8/ADC1_CH7/SUBSPICS1_12") (pintype "passive"))
    )
    (net (code "32") (name "/GPIO9") (class "Default")
      (node (ref "J1") (pin "12") (pinfunction "12_12") (pintype "passive"))
      (node (ref "U1") (pin "13") (pinfunction "GPIO9/RTC_GPIO9/TOUCH9/ADC1_CH8/FSPIHD/SUBSPIHD_13") (pintype "passive"))
    )
    (net (code "33") (name "/GPIO10") (class "Default")
      (node (ref "J1") (pin "13") (pinfunction "13_13") (pintype "passive"))
      (node (ref "U1") (pin "14") (pinfunction "GPIO10/RTC_GPIO10/TOUCH10/ADC1_CH9/FSPICS0/FSPIIO4/SUBSPICS0_14") (pintype "passive"))
    )
    (net (code "34") (name "/GPIO11") (class "Default")
      (node (ref "J1") (pin "14") (pinfunction "14_14") (pintype "passive"))
      (node (ref "U1") (pin "15") (pinfunction "GPIO11/RTC_GPIO11/TOUCH11/ADC2_CH0/FSPID/FSPIIO5/SUBSPID_15") (pintype "passive"))
    )
    (net (code "35") (name "/GPIO12") (class "Default")
      (node (ref "J1") (pin "15") (pinfunction "15_15") (pintype "passive"))
      (node (ref "U1") (pin "16") (pinfunction "GPIO12/RTC_GPIO12/TOUCH12/ADC2_CH1/FSPICLK/FSPIIO6/SUBSPICLK_16") (pintype "passive"))
    )
    (net (code "36") (name "/GPIO13") (class "Default")
      (node (ref "J1") (pin "16") (pinfunction "16_16") (pintype "passive"))
      (node (ref "U1") (pin "17") (pinfunction "GPIO13/RTC_GPIO13/TOUCH13/ADC2_CH2/FSPIQ/FSPIIO7/SUBSPIQ_17") (pintype "passive"))
    )
    (net (code "37") (name "/GPIO14") (class "Default")
      (node (ref "J1") (pin "17") (pinfunction "17_17") (pintype "passive"))
      (node (ref "U1") (pin "18") (pinfunction "GPIO14/RTC_GPIO14/TOUCH14/ADC2_CH3/FSPIWP/FSPIDQS/SUBSPIWP_18") (pintype "passive"))
    )
    (net (code "38") (name "/GPIO15") (class "Default")
      (node (ref "J1") (pin "18") (pinfunction "18_18") (pintype "passive"))
      (node (ref "U1") (pin "19") (pinfunction "GPIO15/RTC_GPIO15/U0RTS/ADC2_CH4/XTAL_32K_P_19") (pintype "passive"))
    )
    (net (code "39") (name "/GPIO16") (class "Default")
      (node (ref "J1") (pin "19") (pinfunction "19_19") (pintype "passive"))
      (node (ref "U1") (pin "20") (pinfunction "GPIO16/RTC_GPIO16/U0CTS/ADC2_CH5/XTAL_32K_N_20") (pintype "passive"))
    )
    (net (code "40") (name "/GPIO17") (class "Default")
      (node (ref "J1") (pin "20") (pinfunction "20_20") (pintype "passive"))
      (node (ref "U1") (pin "21") (pinfunction "GPIO17/RTC_GPIO17/U1TXD/ADC2_CH6_21") (pintype "passive"))
    )
    (net (code "41") (name "/GPIO18") (class "Default")
      (node (ref "J1") (pin "21") (pinfunction "21_21") (pintype "passive"))
      (node (ref "U1") (pin "22") (pinfunction "GPIO18/RTC_GPIO18/U1RXD/ADC2_CH7/CLK_OUT3_22") (pintype "passive"))
    )
    (net (code "42") (name "/GPIO21") (class "Default")
      (node (ref "J2") (pin "19") (pinfunction "19_19") (pintype "passive"))
      (node (ref "U1") (pin "25") (pinfunction "GPIO21/RTC_GPIO21/_25") (pintype "passive"))
    )
    (net (code "43") (name "/GPIO26") (class "Default")
      (node (ref "J2") (pin "18") (pinfunction "18_18") (pintype "passive"))
      (node (ref "U1") (pin "26") (pinfunction "GPIO26/SPICS1_26") (pintype "passive"))
    )
    (net (code "44") (name "/GPIO33") (class "Default")
      (node (ref "J2") (pin "17") (pinfunction "17_17") (pintype "passive"))
      (node (ref "U1") (pin "28") (pinfunction "GPIO33/SPIIO4/FSPIHD/SUBSPIHD_28") (pintype "passive"))
    )
    (net (code "45") (name "/GPIO34") (class "Default")
      (node (ref "J2") (pin "16") (pinfunction "16_16") (pintype "passive"))
      (node (ref "U1") (pin "29") (pinfunction "GPIO34/SPIIO5/FSPICS0/SUBSPICS0_29") (pintype "passive"))
    )
    (net (code "46") (name "/GPIO35") (class "Default")
      (node (ref "J2") (pin "15") (pinfunction "15_15") (pintype "passive"))
      (node (ref "U1") (pin "31") (pinfunction "GPIO35/SPIIO6/FSPID/SUBSPID_31") (pintype "passive"))
    )
    (net (code "47") (name "/GPIO36") (class "Default")
      (node (ref "J2") (pin "14") (pinfunction "14_14") (pintype "passive"))
      (node (ref "U1") (pin "32") (pinfunction "GPIO36/SPIIO7/FSPICLK/SUBSPICLK_32") (pintype "passive"))
    )
    (net (code "48") (name "/GPIO37") (class "Default")
      (node (ref "J2") (pin "13") (pinfunction "13_13") (pintype "passive"))
      (node (ref "U1") (pin "33") (pinfunction "GPIO37/SPIDQS/FSPIQ/SUBSPIQ_33") (pintype "passive"))
    )
    (net (code "49") (name "/GPIO38") (class "Default")
      (node (ref "J2") (pin "12") (pinfunction "12_12") (pintype "passive"))
      (node (ref "U1") (pin "34") (pinfunction "GPIO38/FSPIWP/SUBSPIWP_34") (pintype "passive"))
    )
    (net (code "50") (name "/GPIO39") (class "Default")
      (node (ref "J2") (pin "11") (pinfunction "11_11") (pintype "passive"))
      (node (ref "U1") (pin "35") (pinfunction "GPIO39/MTCK/_CLK_OUT3/SUBSPICS1_35") (pintype "passive"))
    )
    (net (code "51") (name "/GPIO40") (class "Default")
      (node (ref "J2") (pin "10") (pinfunction "10_10") (pintype "passive"))
      (node (ref "U1") (pin "36") (pinfunction "MTDO/GPIO40/CLK_OUT2_36") (pintype "passive"))
    )
    (net (code "52") (name "/GPIO41") (class "Default")
      (node (ref "J2") (pin "9") (pinfunction "9_9") (pintype "passive"))
      (node (ref "U1") (pin "37") (pinfunction "MTDI/_GPIO41/CLK_OUT1_37") (pintype "passive"))
    )
    (net (code "53") (name "/GPIO42") (class "Default")
      (node (ref "J2") (pin "8") (pinfunction "8_8") (pintype "passive"))
      (node (ref "U1") (pin "38") (pinfunction "GPIO42/MTMS_38") (pintype "passive"))
    )
    (net (code "54") (name "/GPIO45") (class "Default")
      (node (ref "J2") (pin "5") (pinfunction "5_5") (pintype "passive"))
      (node (ref "U1") (pin "41") (pinfunction "GPIO45_41") (pintype "passive"))
    )
    (net (code "55") (name "/GPIO46") (class "Default")
      (node (ref "J2") (pin "4") (pinfunction "4_4") (pintype "passive"))
      (node (ref "U1") (pin "44") (pinfunction "GPIO46/U0TXD/CLK_OUT1_44") (pintype "passive"))
    )
    (net (code "56") (name "/GPIO47") (class "Default")
      (node (ref "J2") (pin "23") (pinfunction "23_23") (pintype "passive"))
      (node (ref "U1") (pin "27") (pinfunction "GPIO47/SPICLK_P_DIFF/SUBSPICLK_P_DIFF_27") (pintype "passive"))
    )
    (net (code "57") (name "/GPIO48") (class "Default")
      (node (ref "J2") (pin "22") (pinfunction "22_22") (pintype "passive"))
      (node (ref "U1") (pin "30") (pinfunction "GPIO48/SPICLK_N_DIFF/SUBSPICLK_N_DIFF_30") (pintype "passive"))
    )
    (net (code "58") (name "/RTS_FTDI") (class "Default")
      (node (ref "Q1") (pin "2") (pinfunction "E_2") (pintype "passive"))
      (node (ref "R22") (pin "1") (pinfunction "1_1") (pintype "passive"))
      (node (ref "U2") (pin "19") (pinfunction "~{RTS}_19") (pintype "passive"))
    )
    (net (code "59") (name "/RXD_FTDI") (class "Default")
      (node (ref "R18") (pin "2") (pinfunction "2_2") (pintype "passive"))
      (node (ref "U2") (pin "1") (pinfunction "RXD_1") (pintype "passive"))
    )
    (net (code "60") (name "/TXD_FTDI") (class "Default")
      (node (ref "R19") (pin "2") (pinfunction "2_2") (pintype "passive"))
      (node (ref "U2") (pin "17") (pinfunction "TXD_17") (pintype "passive"))
    )
    (net (code "61") (name "/U0RXD") (class "Default")
      (node (ref "J2") (pin "6") (pinfunction "6_6") (pintype "passive"))
      (node (ref "R19") (pin "1") (pinfunction "1_1") (pintype "passive"))
      (node (ref "U1") (pin "40") (pinfunction "GPIO44/U0RXD/CLK_OUT2_40") (pintype "passive"))
    )
    (net (code "62") (name "/U0TXD") (class "Default")
      (node (ref "J2") (pin "7") (pinfunction "7_7") (pintype "passive"))
      (node (ref "R18") (pin "1") (pinfunction "1_1") (pintype "passive"))
      (node (ref "U1") (pin "39") (pinfunction "GPIO43/U0TXD/CLK_OUT1_39") (pintype "passive"))
    )
    (net (code "63") (name "/VBUS_SENSE") (class "Default")
      (node (ref "R13") (pin "2") (pinfunction "2_2") (pintype "passive"))
      (node (ref "R9") (pin "1") (pinfunction "1_1") (pintype "passive"))
      (node (ref "U2") (pin "16") (pinfunction "CBUS3_16") (pintype "passive"))
    )
    (net (code "64") (name "GND") (class "Default")
      (node (ref "C1") (pin "1") (pinfunction "1_1") (pintype "passive"))
      (node (ref "C10") (pin "1") (pinfunction "1_1") (pintype "passive"))
      (node (ref "C11") (pin "2") (pinfunction "2_2") (pintype "passive"))
      (node (ref "C12") (pin "1") (pinfunction "1_1") (pintype "passive"))
      (node (ref "C13") (pin "1") (pinfunction "1_1") (pintype "passive"))
      (node (ref "C14") (pin "1") (pinfunction "1_1") (pintype "passive"))
      (node (ref "C15") (pin "1") (pinfunction "1_1") (pintype "passive"))
      (node (ref "C16") (pin "1") (pinfunction "1_1") (pintype "passive"))
      (node (ref "C17") (pin "1") (pinfunction "1_1") (pintype "passive"))
      (node (ref "C2") (pin "1") (pinfunction "1_1") (pintype "passive"))
      (node (ref "C3") (pin "1") (pinfunction "1_1") (pintype "passive"))
      (node (ref "C4") (pin "1") (pinfunction "1_1") (pintype "passive"))
      (node (ref "C5") (pin "1") (pinfunction "1_1") (pintype "passive"))
      (node (ref "C6") (pin "1") (pinfunction "1_1") (pintype "passive"))
      (node (ref "C7") (pin "1") (pinfunction "1_1") (pintype "passive"))
      (node (ref "C8") (pin "1") (pinfunction "1_1") (pintype "passive"))
      (node (ref "C9") (pin "1") (pinfunction "1_1") (pintype "passive"))
      (node (ref "D1") (pin "1") (pinfunction "1_1") (pintype "passive"))
      (node (ref "D2") (pin "1") (pinfunction "1_1") (pintype "passive"))
      (node (ref "D3") (pin "1") (pinfunction "1_1") (pintype "passive"))
      (node (ref "D5") (pin "2") (pinfunction "2_2") (pintype "passive"))
      (node (ref "D6") (pin "1") (pinfunction "1_1") (pintype "passive"))
      (node (ref "D7") (pin "1") (pinfunction "1_1") (pintype "passive"))
      (node (ref "D8") (pin "1") (pinfunction "1_1") (pintype "passive"))
      (node (ref "J1") (pin "1") (pinfunction "1_1") (pintype "passive"))
      (node (ref "J1") (pin "23") (pinfunction "23_23") (pintype "passive"))
      (node (ref "J2") (pin "2") (pinfunction "2_2") (pintype "passive"))
      (node (ref "J2") (pin "24") (pinfunction "24_24") (pintype "passive"))
      (node (ref "J3") (pin "A1B12") (pinfunction "GND_A1B12_A1B12") (pintype "passive"))
      (node (ref "J3") (pin "B1A12") (pinfunction "GND_B1A12_B1A12") (pintype "passive"))
      (node (ref "J3") (pin "S1") (pinfunction "SHIELD_1_S1") (pintype "passive"))
      (node (ref "J3") (pin "S2") (pinfunction "SHIELD_2_S2") (pintype "passive"))
      (node (ref "J3") (pin "S3") (pinfunction "SHIELD_3_S3") (pintype "passive"))
      (node (ref "J3") (pin "S4") (pinfunction "SHIELD_4_S4") (pintype "passive"))
      (node (ref "J4") (pin "A1B12") (pinfunction "GND_A1B12_A1B12") (pintype "passive"))
      (node (ref "J4") (pin "B1A12") (pinfunction "GND_B1A12_B1A12") (pintype "passive"))
      (node (ref "J4") (pin "S1") (pinfunction "SHIELD_1_S1") (pintype "passive"))
      (node (ref "J4") (pin "S2") (pinfunction "SHIELD_2_S2") (pintype "passive"))
      (node (ref "J4") (pin "S3") (pinfunction "SHIELD_3_S3") (pintype "passive"))
      (node (ref "J4") (pin "S4") (pinfunction "SHIELD_4_S4") (pintype "passive"))
      (node (ref "R10") (pin "1") (pinfunction "1_1") (pintype "passive"))
      (node (ref "R11") (pin "1") (pinfunction "1_1") (pintype "passive"))
      (node (ref "R12") (pin "1") (pinfunction "1_1") (pintype "passive"))
      (node (ref "R13") (pin "1") (pinfunction "1_1") (pintype "passive"))
      (node (ref "R14") (pin "1") (pinfunction "1_1") (pintype "passive"))
      (node (ref "R15") (pin "1") (pinfunction "1_1") (pintype "passive"))
      (node (ref "SW1") (pin "3") (pinfunction "3_3") (pintype "passive"))
      (node (ref "SW1") (pin "4") (pinfunction "4_4") (pintype "passive"))
      (node (ref "SW2") (pin "3") (pinfunction "3_3") (pintype "passive"))
      (node (ref "SW2") (pin "4") (pinfunction "4_4") (pintype "passive"))
      (node (ref "U1") (pin "1") (pinfunction "GND_1_1") (pintype "passive"))
      (node (ref "U1") (pin "2") (pinfunction "GND_2_2") (pintype "passive"))
      (node (ref "U1") (pin "42") (pinfunction "GND_42_42") (pintype "passive"))
      (node (ref "U1") (pin "43") (pinfunction "GND_43_43") (pintype "passive"))
      (node (ref "U1") (pin "46") (pinfunction "GND_46_46") (pintype "passive"))
      (node (ref "U1") (pin "47") (pinfunction "GND_47_47") (pintype "passive"))
      (node (ref "U1") (pin "48") (pinfunction "GND_48_48") (pintype "passive"))
      (node (ref "U1") (pin "49") (pinfunction "GND_49_49") (pintype "passive"))
      (node (ref "U1") (pin "50") (pinfunction "GND_50_50") (pintype "passive"))
      (node (ref "U1") (pin "51") (pinfunction "GND_51_51") (pintype "passive"))
      (node (ref "U1") (pin "52") (pinfunction "GND_52_52") (pintype "passive"))
      (node (ref "U1") (pin "53") (pinfunction "GND_53_53") (pintype "passive"))
      (node (ref "U1") (pin "54") (pinfunction "GND_54_54") (pintype "passive"))
      (node (ref "U1") (pin "55") (pinfunction "GND_55_55") (pintype "passive"))
      (node (ref "U1") (pin "56") (pinfunction "GND_56_56") (pintype "passive"))
      (node (ref "U1") (pin "57") (pinfunction "GND_57_57") (pintype "passive"))
      (node (ref "U1") (pin "58") (pinfunction "GND_58_58") (pintype "passive"))
      (node (ref "U1") (pin "59") (pinfunction "GND_59_59") (pintype "passive"))
      (node (ref "U1") (pin "60") (pinfunction "GND_60_60") (pintype "passive"))
      (node (ref "U1") (pin "61") (pinfunction "GND_61_61") (pintype "passive"))
      (node (ref "U1") (pin "62") (pinfunction "GND_62_62") (pintype "passive"))
      (node (ref "U1") (pin "63") (pinfunction "GND_63_63") (pintype "passive"))
      (node (ref "U1") (pin "64") (pinfunction "GND_64_64") (pintype "passive"))
      (node (ref "U1") (pin "65") (pinfunction "GND_65_65") (pintype "passive"))
      (node (ref "U1") (pin "66") (pinfunction "GND_66_66") (pintype "passive"))
      (node (ref "U1") (pin "67") (pinfunction "GND_67_67") (pintype "passive"))
      (node (ref "U1") (pin "68") (pinfunction "GND_68_68") (pintype "passive"))
      (node (ref "U1") (pin "69") (pinfunction "GND_69_69") (pintype "passive"))
      (node (ref "U1") (pin "70") (pinfunction "GND_70_70") (pintype "passive"))
      (node (ref "U1") (pin "71") (pinfunction "GND_71_71") (pintype "passive"))
      (node (ref "U1") (pin "72") (pinfunction "GND_72_72") (pintype "passive"))
      (node (ref "U1") (pin "73") (pinfunction "GND_73_73") (pintype "passive"))
      (node (ref "U2") (pin "13") (pinfunction "GND_13") (pintype "passive"))
      (node (ref "U2") (pin "21") (pinfunction "GND_21") (pintype "passive"))
      (node (ref "U2") (pin "3") (pinfunction "GND_3") (pintype "passive"))
      (node (ref "U3") (pin "2") (pinfunction "GND_2") (pintype "power_in"))
      (node (ref "U3") (pin "4") (pinfunction "GND_4") (pintype "power_in"))
    )
    (net (code "65") (name "Net-(D4-Pad1)") (class "Default")
      (node (ref "D4") (pin "1") (pinfunction "1_1") (pintype "passive"))
      (node (ref "R8") (pin "1") (pinfunction "1_1") (pintype "passive"))
    )
    (net (code "66") (name "Net-(D5-Pad1)") (class "Default")
      (node (ref "D5") (pin "1") (pinfunction "1_1") (pintype "passive"))
      (node (ref "R7") (pin "1") (pinfunction "1_1") (pintype "passive"))
    )
    (net (code "67") (name "Net-(J3-CC1)") (class "Default")
      (node (ref "J3") (pin "A5") (pinfunction "CC1_A5") (pintype "passive"))
      (node (ref "R12") (pin "2") (pinfunction "2_2") (pintype "passive"))
    )
    (net (code "68") (name "Net-(J3-CC2)") (class "Default")
      (node (ref "J3") (pin "B5") (pinfunction "CC2_B5") (pintype "passive"))
      (node (ref "R11") (pin "2") (pinfunction "2_2") (pintype "passive"))
    )
    (net (code "69") (name "Net-(J4-CC1)") (class "Default")
      (node (ref "J4") (pin "A5") (pinfunction "CC1_A5") (pintype "passive"))
      (node (ref "R15") (pin "2") (pinfunction "2_2") (pintype "passive"))
    )
    (net (code "70") (name "Net-(J4-CC2)") (class "Default")
      (node (ref "J4") (pin "B5") (pinfunction "CC2_B5") (pintype "passive"))
      (node (ref "R14") (pin "2") (pinfunction "2_2") (pintype "passive"))
    )
    (net (code "71") (name "Net-(Q1-B)") (class "Default")
      (node (ref "Q1") (pin "1") (pinfunction "B_1") (pintype "passive"))
      (node (ref "R17") (pin "2") (pinfunction "2_2") (pintype "passive"))
    )
    (net (code "72") (name "Net-(Q2-B)") (class "Default")
      (node (ref "Q2") (pin "1") (pinfunction "B_1") (pintype "passive"))
      (node (ref "R22") (pin "2") (pinfunction "2_2") (pintype "passive"))
    )
    (net (code "73") (name "Net-(U2-CBUS0)") (class "Default")
      (node (ref "R10") (pin "2") (pinfunction "2_2") (pintype "passive"))
      (node (ref "U2") (pin "15") (pinfunction "CBUS0_15") (pintype "passive"))
    )
    (net (code "74") (name "unconnected-(J1-Pad24)") (class "Default")
      (node (ref "J1") (pin "24") (pinfunction "24_24") (pintype "passive+no_connect"))
    )
    (net (code "75") (name "unconnected-(J3-SBU1-PadA8)") (class "Default")
      (node (ref "J3") (pin "A8") (pinfunction "SBU1_A8") (pintype "passive+no_connect"))
    )
    (net (code "76") (name "unconnected-(J3-SBU2-PadB8)") (class "Default")
      (node (ref "J3") (pin "B8") (pinfunction "SBU2_B8") (pintype "passive+no_connect"))
    )
    (net (code "77") (name "unconnected-(J4-SBU1-PadA8)") (class "Default")
      (node (ref "J4") (pin "A8") (pinfunction "SBU1_A8") (pintype "passive+no_connect"))
    )
    (net (code "78") (name "unconnected-(J4-SBU2-PadB8)") (class "Default")
      (node (ref "J4") (pin "B8") (pinfunction "SBU2_B8") (pintype "passive+no_connect"))
    )
    (net (code "79") (name "unconnected-(U2-CBUS1-Pad14)") (class "Default")
      (node (ref "U2") (pin "14") (pinfunction "CBUS1_14") (pintype "passive+no_connect"))
    )
    (net (code "80") (name "unconnected-(U2-CBUS2-Pad7)") (class "Default")
      (node (ref "U2") (pin "7") (pinfunction "CBUS2_7") (pintype "passive+no_connect"))
    )
    (net (code "81") (name "unconnected-(U2-~{CTS}-Pad6)") (class "Default")
      (node (ref "U2") (pin "6") (pinfunction "~{CTS}_6") (pintype "passive+no_connect"))
    )
    (net (code "82") (name "unconnected-(U2-~{DCD}-Pad5)") (class "Default")
      (node (ref "U2") (pin "5") (pinfunction "~{DCD}_5") (pintype "passive+no_connect"))
    )
    (net (code "83") (name "unconnected-(U2-~{DSR}-Pad4)") (class "Default")
      (node (ref "U2") (pin "4") (pinfunction "~{DSR}_4") (pintype "passive+no_connect"))
    )
    (net (code "84") (name "unconnected-(U2-~{RI}-Pad2)") (class "Default")
      (node (ref "U2") (pin "2") (pinfunction "~{RI}_2") (pintype "passive+no_connect"))
    )
  )
)
